# LSM9DS0.net
KiCad netlist of a schematic drawn in EAGLE
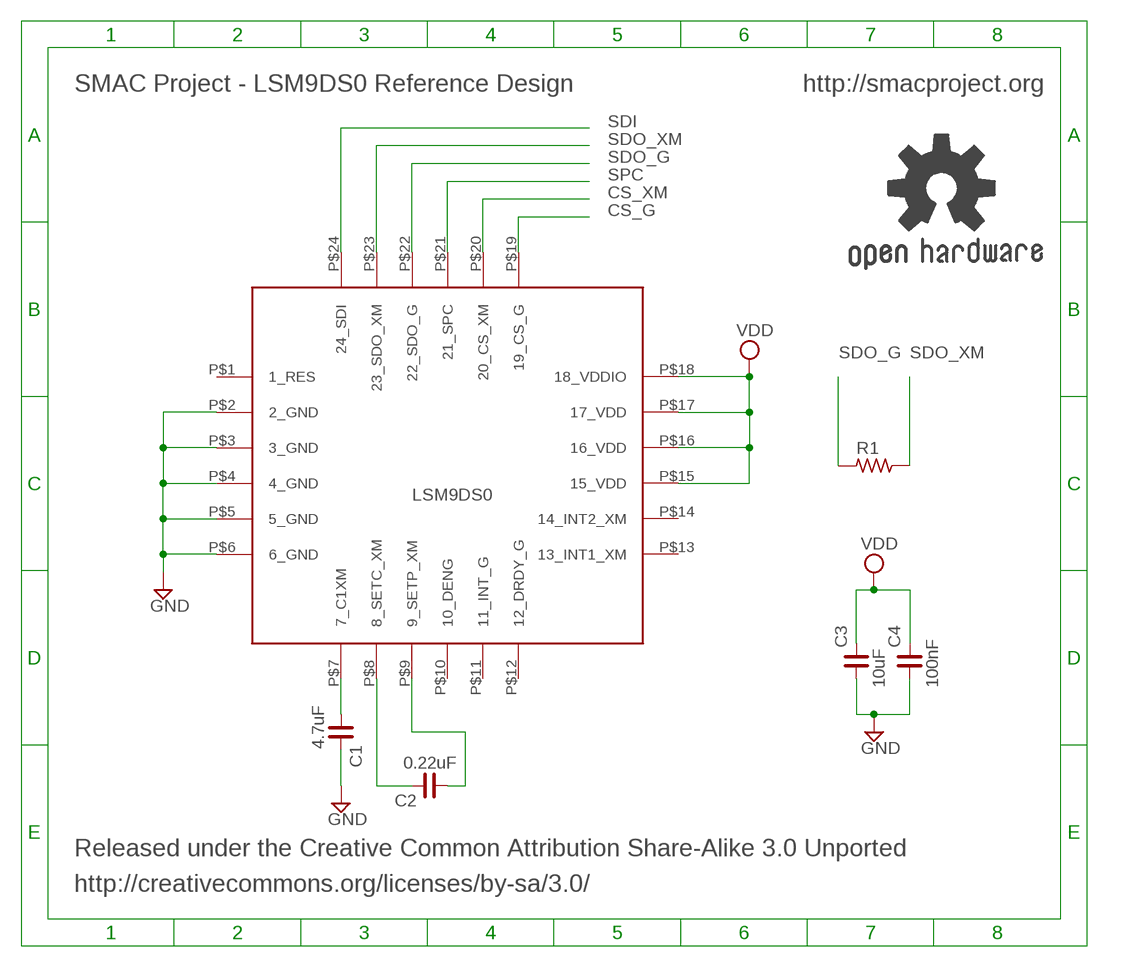
[diagram p0: schematic, sheet 1]

(export (version "E")
  (design (tool "Eeschema 10.0.6"))
  (components
    (comp (ref "C1")
      (value "4.7uF")
      (footprint "eagle-import:C0402")
      (libsource (lib "eagle-import") (part "C_0402"))
    )
    (comp (ref "C2")
      (value "0.22uF")
      (footprint "eagle-import:C0402")
      (libsource (lib "eagle-import") (part "C_0402"))
    )
    (comp (ref "C3")
      (value "10uF")
      (footprint "eagle-import:C0402")
      (libsource (lib "eagle-import") (part "C_0402"))
    )
    (comp (ref "C4")
      (value "100nF")
      (footprint "eagle-import:C0402")
      (libsource (lib "eagle-import") (part "C_0402"))
    )
    (comp (ref "GOLD_ORB_SM2")
      (value "OSHWLOGO_REF_SM")
      (footprint "eagle-import:OSHW2REF")
      (libsource (lib "eagle-import") (part "OSHWLOGO_REF_SM"))
    )
    (comp (ref "R1")
      (value "R_0402")
      (footprint "eagle-import:R0402")
      (libsource (lib "eagle-import") (part "R_0402"))
    )
    (comp (ref "U$1")
      (value "LSM9DS09DOFS0")
      (footprint "eagle-import:LGA24(4X4X1)")
      (libsource (lib "eagle-import") (part "LSM9DS09DOFS0"))
    )
  )
  (nets
    (net (code "1") (name "/CS_G") (class "Default")
      (node (ref "U$1") (pin "P$19") (pinfunction "19_CS_G_P$19") (pintype "bidirectional"))
    )
    (net (code "2") (name "/CS_XM") (class "Default")
      (node (ref "U$1") (pin "P$20") (pinfunction "20_CS_XM_P$20") (pintype "bidirectional"))
    )
    (net (code "3") (name "/SDI") (class "Default")
      (node (ref "U$1") (pin "P$24") (pinfunction "24_SDI_P$24") (pintype "bidirectional"))
    )
    (net (code "4") (name "/SDO_G") (class "Default")
      (node (ref "R1") (pin "1") (pinfunction "1_1") (pintype "passive"))
      (node (ref "U$1") (pin "P$22") (pinfunction "22_SDO_G_P$22") (pintype "bidirectional"))
    )
    (net (code "5") (name "/SDO_XM") (class "Default")
      (node (ref "R1") (pin "2") (pinfunction "2_2") (pintype "passive"))
      (node (ref "U$1") (pin "P$23") (pinfunction "23_SDO_XM_P$23") (pintype "bidirectional"))
    )
    (net (code "6") (name "/SPC") (class "Default")
      (node (ref "U$1") (pin "P$21") (pinfunction "21_SPC_P$21") (pintype "bidirectional"))
    )
    (net (code "7") (name "GND") (class "Default")
      (node (ref "C1") (pin "2") (pinfunction "2_2") (pintype "passive"))
      (node (ref "C3") (pin "1") (pinfunction "1_1") (pintype "passive"))
      (node (ref "C4") (pin "1") (pinfunction "1_1") (pintype "passive"))
      (node (ref "U$1") (pin "P$2") (pinfunction "2_GND_P$2") (pintype "bidirectional"))
      (node (ref "U$1") (pin "P$3") (pinfunction "3_GND_P$3") (pintype "bidirectional"))
      (node (ref "U$1") (pin "P$4") (pinfunction "4_GND_P$4") (pintype "bidirectional"))
      (node (ref "U$1") (pin "P$5") (pinfunction "5_GND_P$5") (pintype "bidirectional"))
      (node (ref "U$1") (pin "P$6") (pinfunction "6_GND_P$6") (pintype "bidirectional"))
    )
    (net (code "8") (name "Net-(U$1-7_C1XM)") (class "Default")
      (node (ref "C1") (pin "1") (pinfunction "1_1") (pintype "passive"))
      (node (ref "U$1") (pin "P$7") (pinfunction "7_C1XM_P$7") (pintype "bidirectional"))
    )
    (net (code "9") (name "Net-(U$1-8_SETC_XM)") (class "Default")
      (node (ref "C2") (pin "2") (pinfunction "2_2") (pintype "passive"))
      (node (ref "U$1") (pin "P$8") (pinfunction "8_SETC_XM_P$8") (pintype "bidirectional"))
    )
    (net (code "10") (name "Net-(U$1-9_SETP_XM)") (class "Default")
      (node (ref "C2") (pin "1") (pinfunction "1_1") (pintype "passive"))
      (node (ref "U$1") (pin "P$9") (pinfunction "9_SETP_XM_P$9") (pintype "bidirectional"))
    )
    (net (code "11") (name "VDD") (class "Default")
      (node (ref "C3") (pin "2") (pinfunction "2_2") (pintype "passive"))
      (node (ref "C4") (pin "2") (pinfunction "2_2") (pintype "passive"))
      (node (ref "U$1") (pin "P$15") (pinfunction "15_VDD_P$15") (pintype "bidirectional"))
      (node (ref "U$1") (pin "P$16") (pinfunction "16_VDD_P$16") (pintype "bidirectional"))
      (node (ref "U$1") (pin "P$17") (pinfunction "17_VDD_P$17") (pintype "bidirectional"))
      (node (ref "U$1") (pin "P$18") (pinfunction "18_VDDIO_P$18") (pintype "bidirectional"))
    )
    (net (code "12") (name "unconnected-(U$1-1_RES-PadP$1)") (class "Default")
      (node (ref "U$1") (pin "P$1") (pinfunction "1_RES_P$1") (pintype "bidirectional"))
    )
    (net (code "13") (name "unconnected-(U$1-10_DENG-PadP$10)") (class "Default")
      (node (ref "U$1") (pin "P$10") (pinfunction "10_DENG_P$10") (pintype "bidirectional"))
    )
    (net (code "14") (name "unconnected-(U$1-11_INT_G-PadP$11)") (class "Default")
      (node (ref "U$1") (pin "P$11") (pinfunction "11_INT_G_P$11") (pintype "bidirectional"))
    )
    (net (code "15") (name "unconnected-(U$1-12_DRDY_G-PadP$12)") (class "Default")
      (node (ref "U$1") (pin "P$12") (pinfunction "12_DRDY_G_P$12") (pintype "bidirectional"))
    )
    (net (code "16") (name "unconnected-(U$1-13_INT1_XM-PadP$13)") (class "Default")
      (node (ref "U$1") (pin "P$13") (pinfunction "13_INT1_XM_P$13") (pintype "bidirectional"))
    )
    (net (code "17") (name "unconnected-(U$1-14_INT2_XM-PadP$14)") (class "Default")
      (node (ref "U$1") (pin "P$14") (pinfunction "14_INT2_XM_P$14") (pintype "bidirectional"))
    )
  )
)
